# Schematic.net
KiCad netlist of a schematic drawn in EAGLE
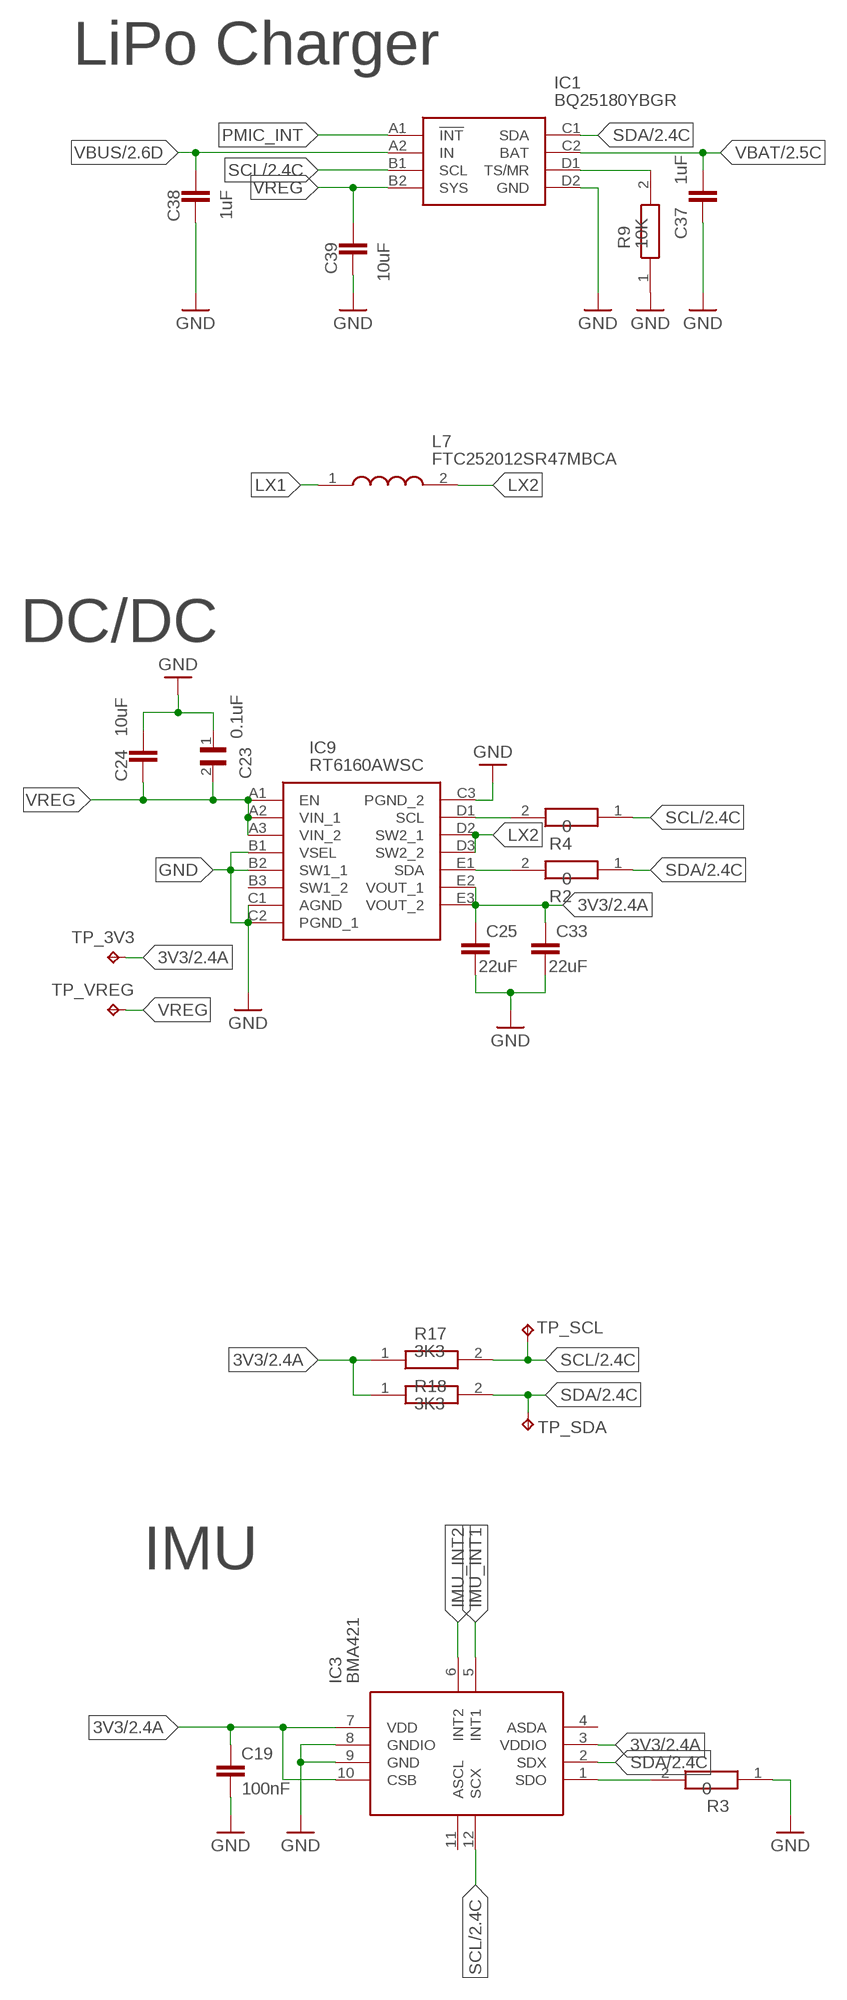
[diagram p0: schematic, sheet 1, part 1 of 2]
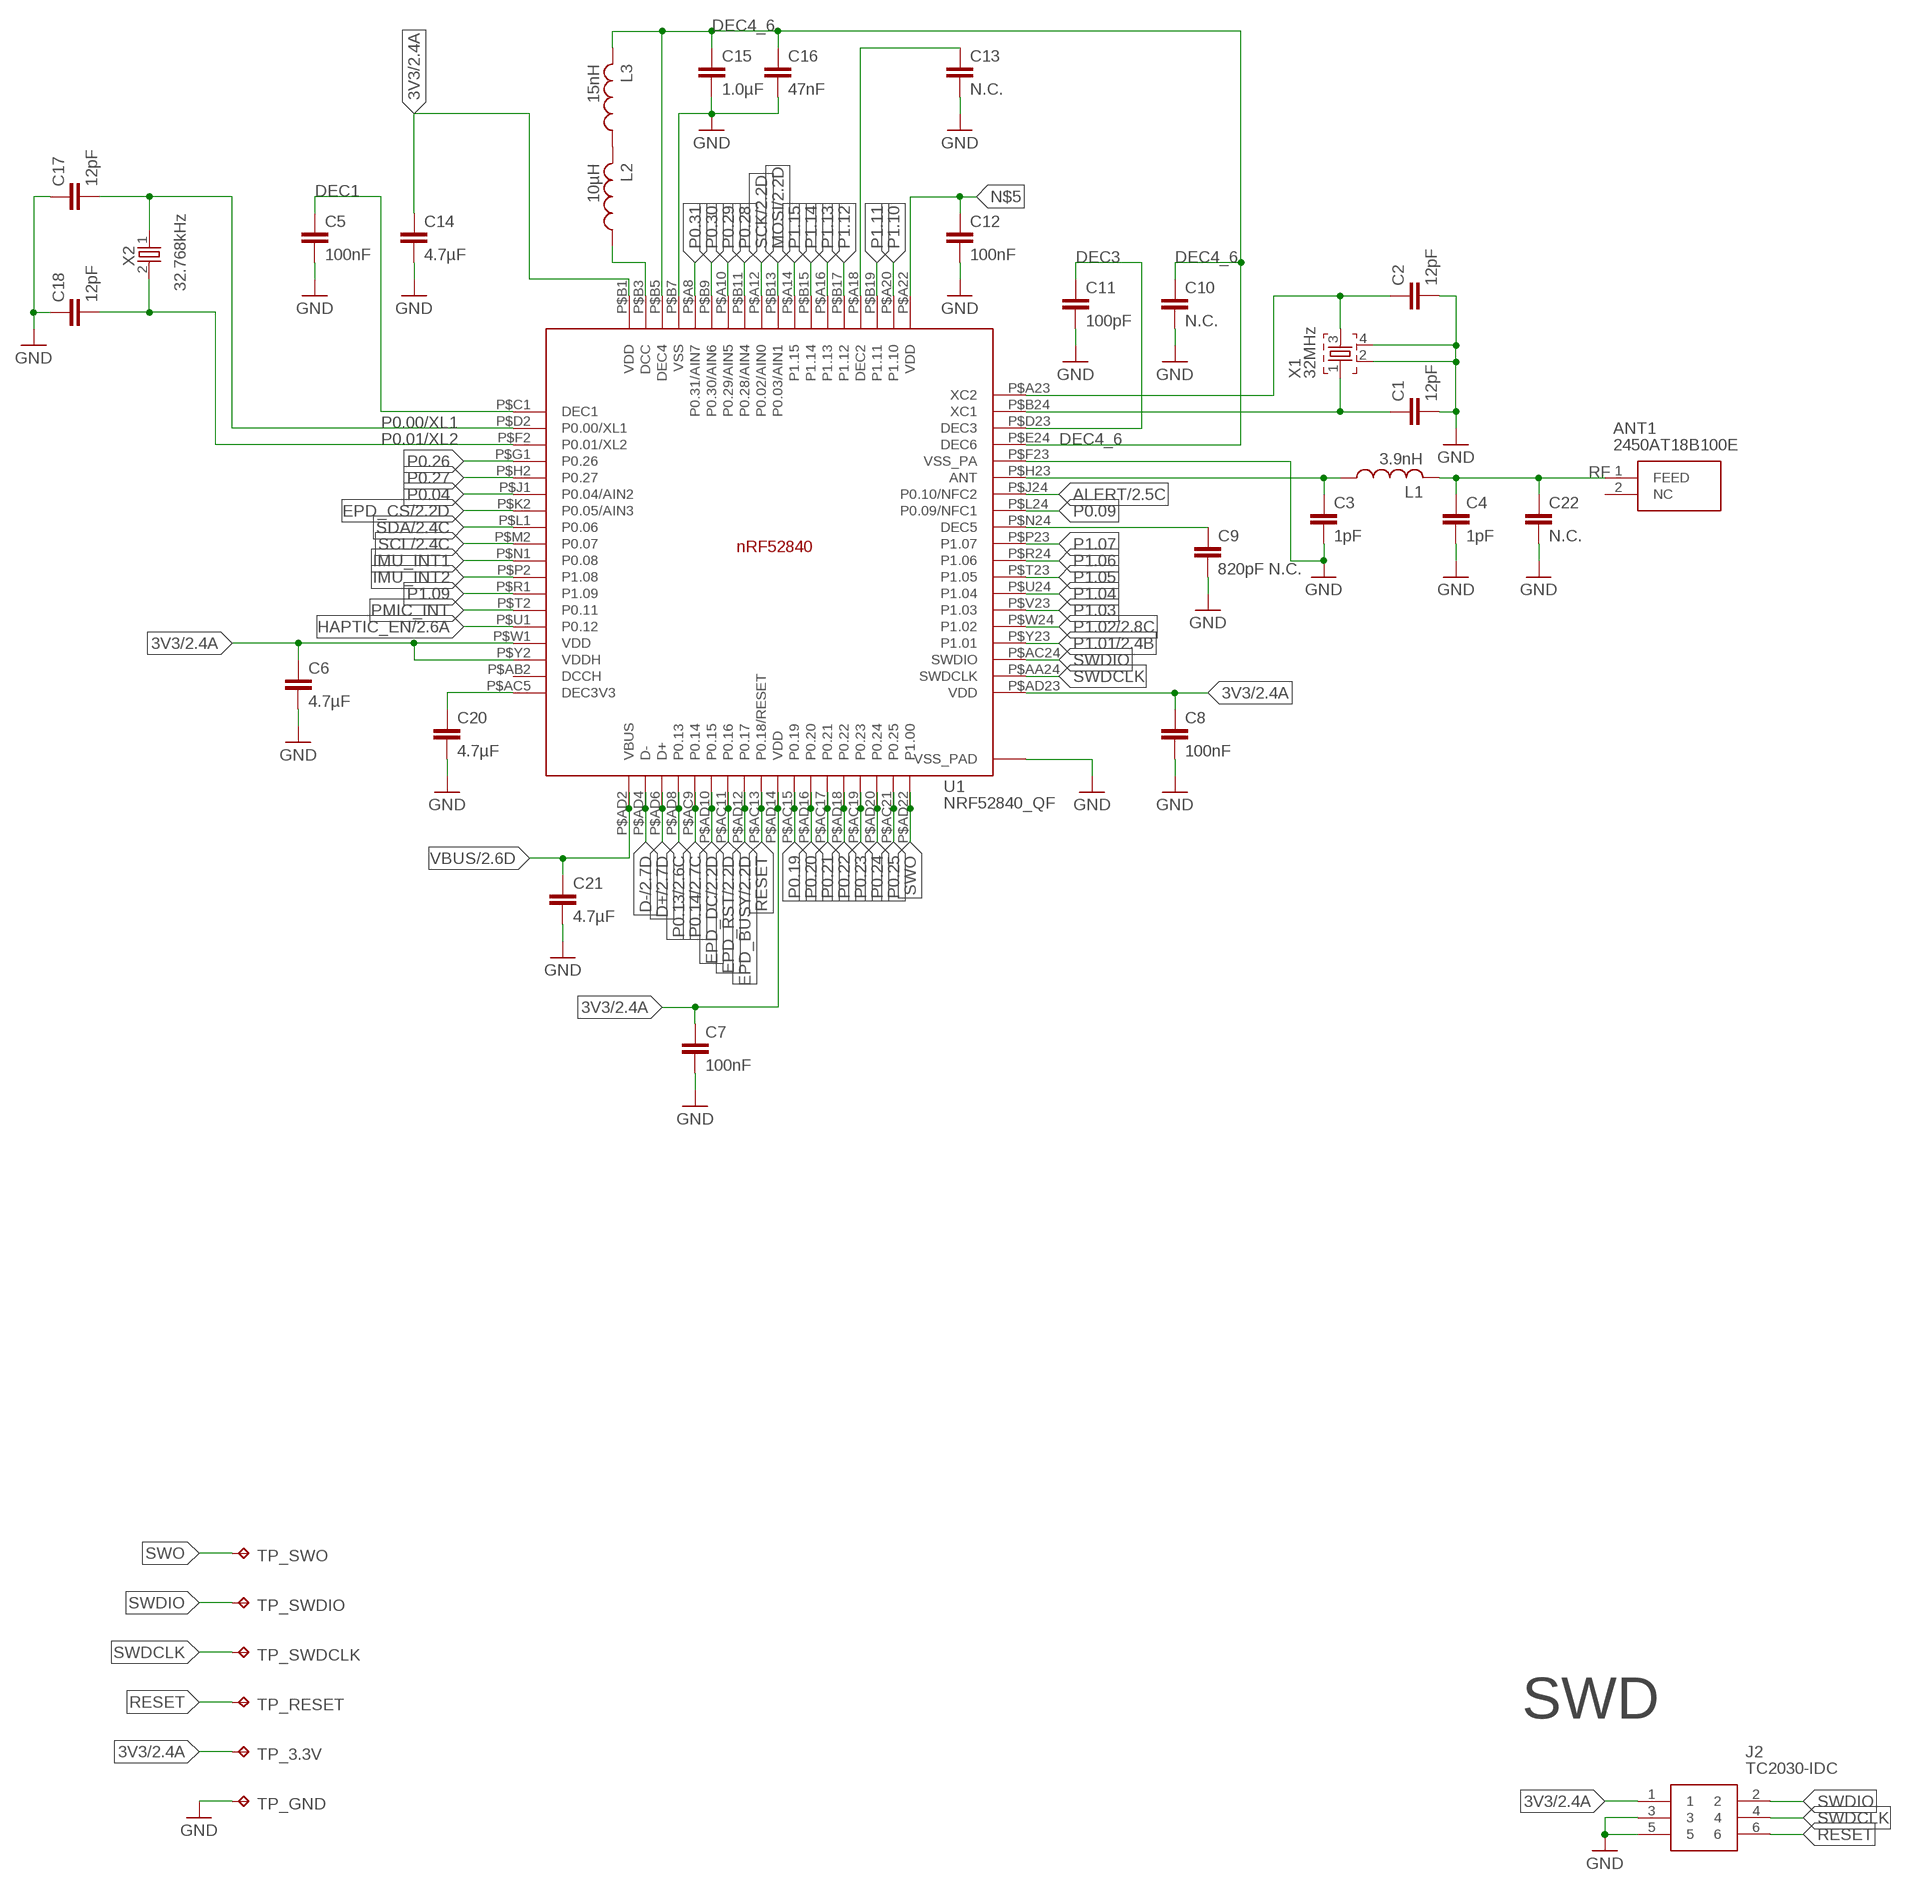
[diagram p1: schematic, sheet 1, part 2 of 2]
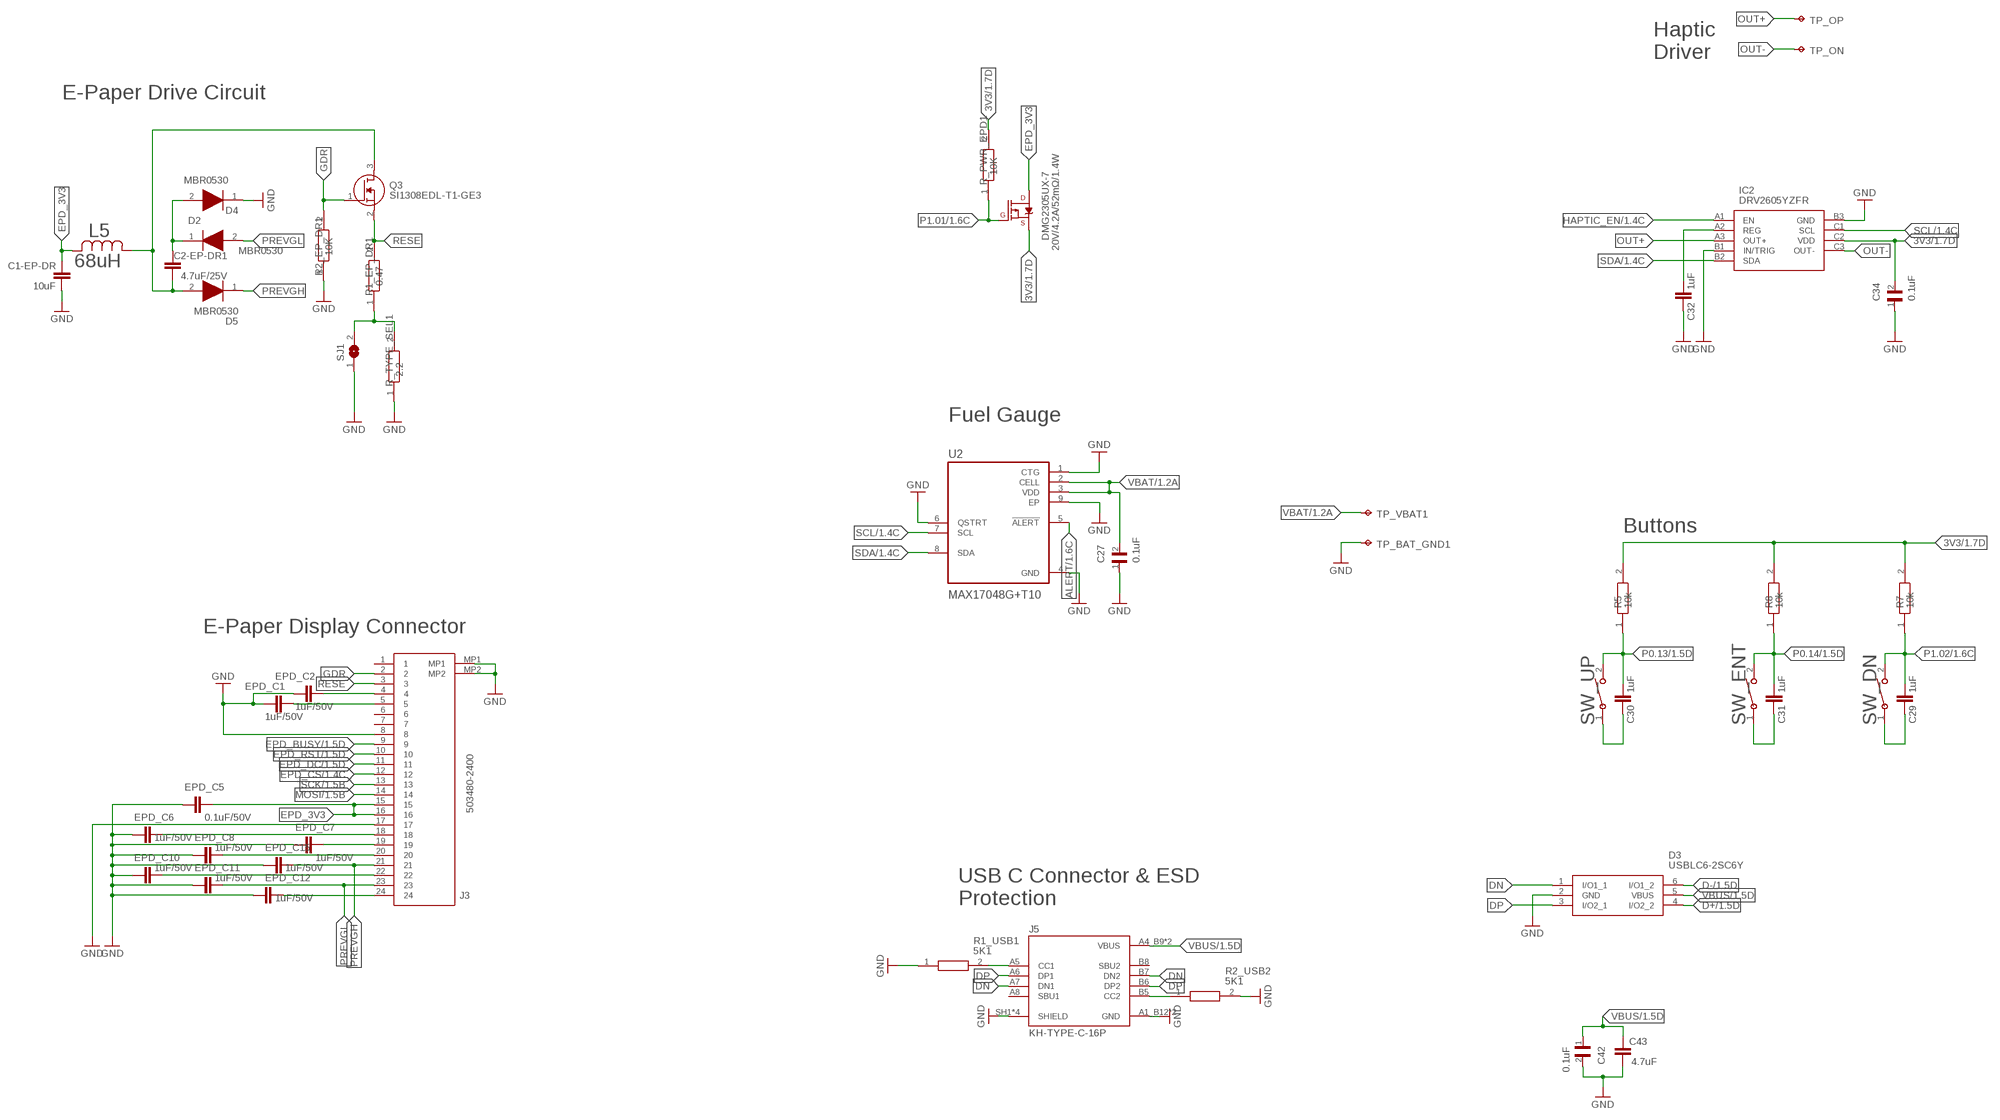
[diagram p2: schematic, sheet 2]

(export (version "E")
  (design (tool "Eeschema 10.0.6"))
  (components
    (comp (ref "ANT1")
      (value "2450AT18B100E")
      (footprint "eagle-import:2450AT18B100E_ANTC3216X140N")
      (fields (field (name "MOUSER_PART_NUMBER") "609-2450AT18B100E"))
      (libsource (lib "eagle-import") (part "2450AT18B100E_2450AT18B100E"))
    )
    (comp (ref "C1")
      (value "12pF")
      (footprint "eagle-import:NORDIC_NRF_3_RESC0201_L")
      (libsource (lib "eagle-import") (part "NORDIC_NRF_3_CAPACITOR_0201_L"))
    )
    (comp (ref "C2")
      (value "12pF")
      (footprint "eagle-import:NORDIC_NRF_3_RESC0201_L")
      (libsource (lib "eagle-import") (part "NORDIC_NRF_3_CAPACITOR_0201_L"))
    )
    (comp (ref "C3")
      (value "1pF")
      (footprint "eagle-import:NORDIC_NRF_3_RESC0201_L")
      (libsource (lib "eagle-import") (part "NORDIC_NRF_3_CAPACITOR_0201_L"))
    )
    (comp (ref "C4")
      (value "1pF")
      (footprint "eagle-import:NORDIC_NRF_3_RESC0201_L")
      (libsource (lib "eagle-import") (part "NORDIC_NRF_3_CAPACITOR_0201_L"))
    )
    (comp (ref "C5")
      (value "100nF")
      (footprint "eagle-import:NORDIC_NRF_3_RESC0201_L")
      (libsource (lib "eagle-import") (part "NORDIC_NRF_3_CAPACITOR_0201_L"))
    )
    (comp (ref "C6")
      (value "4.7µF")
      (footprint "eagle-import:PERFECT_0402_0402")
      (libsource (lib "eagle-import") (part "PERFECT_0402_CAP_0402"))
    )
    (comp (ref "C7")
      (value "100nF")
      (footprint "eagle-import:NORDIC_NRF_3_RESC0201_L")
      (libsource (lib "eagle-import") (part "NORDIC_NRF_3_CAPACITOR_0201_L"))
    )
    (comp (ref "C8")
      (value "100nF")
      (footprint "eagle-import:NORDIC_NRF_3_RESC0201_L")
      (libsource (lib "eagle-import") (part "NORDIC_NRF_3_CAPACITOR_0201_L"))
    )
    (comp (ref "C9")
      (value "820pF N.C.")
      (footprint "eagle-import:NORDIC_NRF_3_RESC0201_L")
      (libsource (lib "eagle-import") (part "NORDIC_NRF_3_CAPACITOR_0201_L"))
    )
    (comp (ref "C10")
      (value "N.C.")
      (footprint "eagle-import:PERFECT_0402_0402")
      (libsource (lib "eagle-import") (part "PERFECT_0402_CAP_0402"))
    )
    (comp (ref "C11")
      (value "100pF")
      (footprint "eagle-import:NORDIC_NRF_3_RESC0201_L")
      (libsource (lib "eagle-import") (part "NORDIC_NRF_3_CAPACITOR_0201_L"))
    )
    (comp (ref "C12")
      (value "100nF")
      (footprint "eagle-import:NORDIC_NRF_3_RESC0201_L")
      (libsource (lib "eagle-import") (part "NORDIC_NRF_3_CAPACITOR_0201_L"))
    )
    (comp (ref "C13")
      (value "N.C.")
      (footprint "eagle-import:PERFECT_0402_0402")
      (libsource (lib "eagle-import") (part "PERFECT_0402_CAP_0402"))
    )
    (comp (ref "C14")
      (value "4.7µF")
      (footprint "eagle-import:PERFECT_0402_0402")
      (libsource (lib "eagle-import") (part "PERFECT_0402_CAP_0402"))
    )
    (comp (ref "C15")
      (value "1.0µF")
      (footprint "eagle-import:PERFECT_0402_0402")
      (libsource (lib "eagle-import") (part "PERFECT_0402_CAP_0402"))
    )
    (comp (ref "C16")
      (value "47nF")
      (footprint "eagle-import:NORDIC_NRF_3_RESC0201_L")
      (libsource (lib "eagle-import") (part "NORDIC_NRF_3_CAPACITOR_0201_L"))
    )
    (comp (ref "C17")
      (value "12pF")
      (footprint "eagle-import:NORDIC_NRF_3_RESC0201_L")
      (libsource (lib "eagle-import") (part "NORDIC_NRF_3_CAPACITOR_0201_L"))
    )
    (comp (ref "C18")
      (value "12pF")
      (footprint "eagle-import:NORDIC_NRF_3_RESC0201_L")
      (libsource (lib "eagle-import") (part "NORDIC_NRF_3_CAPACITOR_0201_L"))
    )
    (comp (ref "C19")
      (value "100nF")
      (footprint "eagle-import:NORDIC_NRF_3_RESC0201_L")
      (libsource (lib "eagle-import") (part "NORDIC_NRF_3_CAPACITOR_0201_L"))
    )
    (comp (ref "C20")
      (value "4.7µF")
      (footprint "eagle-import:PERFECT_0402_0402")
      (libsource (lib "eagle-import") (part "PERFECT_0402_CAP_0402"))
    )
    (comp (ref "C21")
      (value "4.7µF")
      (footprint "eagle-import:PERFECT_0402_0402")
      (libsource (lib "eagle-import") (part "PERFECT_0402_CAP_0402"))
    )
    (comp (ref "C22")
      (value "N.C.")
      (footprint "eagle-import:PERFECT_0402_0402")
      (libsource (lib "eagle-import") (part "PERFECT_0402_CAP_0402"))
    )
    (comp (ref "C23")
      (value "0.1uF")
      (footprint "eagle-import:GRM011R60J152KE01L_1_0201")
      (libsource (lib "eagle-import") (part "GRM011R60J152KE01L_1_GRM011R60J152KE01L"))
    )
    (comp (ref "C24")
      (value "10uF")
      (footprint "eagle-import:PERFECT_0402_0402")
      (libsource (lib "eagle-import") (part "PERFECT_0402_CAP_0402"))
    )
    (comp (ref "C25")
      (value "22uF")
      (footprint "eagle-import:PERFECT_0402_0402")
      (libsource (lib "eagle-import") (part "PERFECT_0402_CAP_0402"))
    )
    (comp (ref "C33")
      (value "22uF")
      (footprint "eagle-import:PERFECT_0402_0402")
      (libsource (lib "eagle-import") (part "PERFECT_0402_CAP_0402"))
    )
    (comp (ref "C37")
      (value "1uF")
      (footprint "eagle-import:PERFECT_0402_0402")
      (libsource (lib "eagle-import") (part "PERFECT_0402_CAP_0402"))
    )
    (comp (ref "C38")
      (value "1uF")
      (footprint "eagle-import:PERFECT_0402_0402")
      (libsource (lib "eagle-import") (part "PERFECT_0402_CAP_0402"))
    )
    (comp (ref "C39")
      (value "10uF")
      (footprint "eagle-import:PERFECT_0402_0402")
      (libsource (lib "eagle-import") (part "PERFECT_0402_CAP_0402"))
    )
    (comp (ref "IC1")
      (value "BQ25180YBGR")
      (footprint "eagle-import:BQ25180YBGR_BGA8C40P2X4_100X155X50")
      (fields (field (name "MOUSER_PART_NUMBER") "595-BQ25180YBGR"))
      (libsource (lib "eagle-import") (part "BQ25180YBGR_BQ25180YBGR"))
    )
    (comp (ref "IC3")
      (value "BMA421")
      (footprint "eagle-import:BMA423_BMA423")
      (fields (field (name "ARROW_PART_NUMBER") "BMA423") (field (name "MOUSER_PART_NUMBER") "262-BMA423"))
      (libsource (lib "eagle-import") (part "BMA423_BMA423"))
    )
    (comp (ref "IC9")
      (value "RT6160AWSC")
      (footprint "eagle-import:RT6160AWSC_BGA15C40P3X5_140X230X60")
      (fields (field (name "MOUSER_PART_NUMBER") "835-RT6160AWSC"))
      (libsource (lib "eagle-import") (part "RT6160AWSC_RT6160AWSC"))
    )
    (comp (ref "J2")
      (value "TC2030-IDC")
      (footprint "eagle-import:TC2030-IDC_TC2030IDC")
      (libsource (lib "eagle-import") (part "TC2030-IDC_TC2030-IDC"))
    )
    (comp (ref "L1")
      (value "3.9nH")
      (footprint "eagle-import:NORDIC_NRF_2_RESC0402_L")
      (libsource (lib "eagle-import") (part "NORDIC_NRF_2_INDUCTOR_0402_L"))
    )
    (comp (ref "L2")
      (value "10µH")
      (footprint "eagle-import:NORDIC_NRF_2_RESC0402_L")
      (libsource (lib "eagle-import") (part "NORDIC_NRF_2_INDUCTOR_0402_L"))
    )
    (comp (ref "L3")
      (value "15nH")
      (footprint "eagle-import:NORDIC_NRF_2_RESC0402_L")
      (libsource (lib "eagle-import") (part "NORDIC_NRF_2_INDUCTOR_0402_L"))
    )
    (comp (ref "L7")
      (value "FTC252012SR47MBCA")
      (footprint "eagle-import:MLP2016SR47MT0S1_INDC2016X100N")
      (libsource (lib "eagle-import") (part "MLP2016SR47MT0S1_FTC252012SR47MBCA"))
    )
    (comp (ref "R2")
      (value "0")
      (footprint "eagle-import:CPF0201D7K68C1_0201")
      (libsource (lib "eagle-import") (part "CPF0201D7K68C1_CPF0201D7K68C1"))
    )
    (comp (ref "R3")
      (value "0")
      (footprint "eagle-import:CPF0201D7K68C1_0201")
      (libsource (lib "eagle-import") (part "CPF0201D7K68C1_CPF0201D7K68C1"))
    )
    (comp (ref "R4")
      (value "0")
      (footprint "eagle-import:CPF0201D7K68C1_0201")
      (libsource (lib "eagle-import") (part "CPF0201D7K68C1_CPF0201D7K68C1"))
    )
    (comp (ref "R9")
      (value "10K")
      (footprint "eagle-import:CPF0201D7K68C1_0201")
      (libsource (lib "eagle-import") (part "CPF0201D7K68C1_CPF0201D7K68C1"))
    )
    (comp (ref "R17")
      (value "3K3")
      (footprint "eagle-import:CPF0201D7K68C1_0201")
      (libsource (lib "eagle-import") (part "CPF0201D7K68C1_CPF0201D7K68C1"))
    )
    (comp (ref "R18")
      (value "3K3")
      (footprint "eagle-import:CPF0201D7K68C1_0201")
      (libsource (lib "eagle-import") (part "CPF0201D7K68C1_CPF0201D7K68C1"))
    )
    (comp (ref "TP_3.3V")
      (value "HECTOR_WATCH_1_TPTP20R")
      (footprint "eagle-import:HECTOR_WATCH_1_TP20R")
      (libsource (lib "eagle-import") (part "HECTOR_WATCH_1_TPTP20R"))
    )
    (comp (ref "TP_3V3")
      (value "HECTOR_WATCH_1_TPTP20R")
      (footprint "eagle-import:HECTOR_WATCH_1_TP20R")
      (libsource (lib "eagle-import") (part "HECTOR_WATCH_1_TPTP20R"))
    )
    (comp (ref "TP_GND")
      (value "HECTOR_WATCH_1_TPTP20R")
      (footprint "eagle-import:HECTOR_WATCH_1_TP20R")
      (libsource (lib "eagle-import") (part "HECTOR_WATCH_1_TPTP20R"))
    )
    (comp (ref "TP_RESET")
      (value "HECTOR_WATCH_1_TPTP20R")
      (footprint "eagle-import:HECTOR_WATCH_1_TP20R")
      (libsource (lib "eagle-import") (part "HECTOR_WATCH_1_TPTP20R"))
    )
    (comp (ref "TP_SCL")
      (value "HECTOR_WATCH_1_TPTP20R")
      (footprint "eagle-import:HECTOR_WATCH_1_TP20R")
      (libsource (lib "eagle-import") (part "HECTOR_WATCH_1_TPTP20R"))
    )
    (comp (ref "TP_SDA")
      (value "HECTOR_WATCH_1_TPTP20R")
      (footprint "eagle-import:HECTOR_WATCH_1_TP20R")
      (libsource (lib "eagle-import") (part "HECTOR_WATCH_1_TPTP20R"))
    )
    (comp (ref "TP_SWDCLK")
      (value "HECTOR_WATCH_1_TPTP20R")
      (footprint "eagle-import:HECTOR_WATCH_1_TP20R")
      (libsource (lib "eagle-import") (part "HECTOR_WATCH_1_TPTP20R"))
    )
    (comp (ref "TP_SWDIO")
      (value "HECTOR_WATCH_1_TPTP20R")
      (footprint "eagle-import:HECTOR_WATCH_1_TP20R")
      (libsource (lib "eagle-import") (part "HECTOR_WATCH_1_TPTP20R"))
    )
    (comp (ref "TP_SWO")
      (value "HECTOR_WATCH_1_TPTP20R")
      (footprint "eagle-import:HECTOR_WATCH_1_TP20R")
      (libsource (lib "eagle-import") (part "HECTOR_WATCH_1_TPTP20R"))
    )
    (comp (ref "TP_VREG")
      (value "HECTOR_WATCH_1_TPTP20R")
      (footprint "eagle-import:HECTOR_WATCH_1_TP20R")
      (libsource (lib "eagle-import") (part "HECTOR_WATCH_1_TPTP20R"))
    )
    (comp (ref "U1")
      (value "NRF52840_QF")
      (footprint "eagle-import:NORDIC_NRF_4_AQFN50P700X700X85_HS-74N")
      (libsource (lib "eagle-import") (part "NORDIC_NRF_4_NRF52840_QF"))
    )
    (comp (ref "X1")
      (value "32MHz")
      (footprint "eagle-import:NORDIC_NRF_BT-XTAL_2016_N")
      (libsource (lib "eagle-import") (part "NORDIC_NRF_XTAL_32MHZ"))
    )
    (comp (ref "X2")
      (value "32.768kHz")
      (footprint "eagle-import:NORDIC_NRF_1_XTAL_3215_N")
      (libsource (lib "eagle-import") (part "NORDIC_NRF_1_XTAL_32KHZ"))
    )
    (comp (ref "C1-EP-DR")
      (value "10uF")
      (footprint "eagle-import:PERFECT_0402_0402")
      (libsource (lib "eagle-import") (part "PERFECT_0402_CAP_0402"))
    )
    (comp (ref "C2-EP-DR1")
      (value "4.7uF/25V")
      (footprint "eagle-import:PERFECT_0402_0402")
      (libsource (lib "eagle-import") (part "PERFECT_0402_CAP_0402"))
    )
    (comp (ref "C27")
      (value "0.1uF")
      (footprint "eagle-import:GRM011R60J152KE01L_1_0201")
      (libsource (lib "eagle-import") (part "GRM011R60J152KE01L_1_GRM011R60J152KE01L"))
    )
    (comp (ref "C29")
      (value "1uF")
      (footprint "eagle-import:PERFECT_0402_0402")
      (libsource (lib "eagle-import") (part "PERFECT_0402_CAP_0402"))
    )
    (comp (ref "C30")
      (value "1uF")
      (footprint "eagle-import:PERFECT_0402_0402")
      (libsource (lib "eagle-import") (part "PERFECT_0402_CAP_0402"))
    )
    (comp (ref "C31")
      (value "1uF")
      (footprint "eagle-import:PERFECT_0402_0402")
      (libsource (lib "eagle-import") (part "PERFECT_0402_CAP_0402"))
    )
    (comp (ref "C32")
      (value "1uF")
      (footprint "eagle-import:PERFECT_0402_0402")
      (libsource (lib "eagle-import") (part "PERFECT_0402_CAP_0402"))
    )
    (comp (ref "C34")
      (value "0.1uF")
      (footprint "eagle-import:GRM011R60J152KE01L_1_0201")
      (libsource (lib "eagle-import") (part "GRM011R60J152KE01L_1_GRM011R60J152KE01L"))
    )
    (comp (ref "C42")
      (value "0.1uF")
      (footprint "eagle-import:GRM011R60J152KE01L_1_0201")
      (libsource (lib "eagle-import") (part "GRM011R60J152KE01L_1_GRM011R60J152KE01L"))
    )
    (comp (ref "C43")
      (value "4.7uF")
      (footprint "eagle-import:PERFECT_0402_0402")
      (libsource (lib "eagle-import") (part "PERFECT_0402_CAP_0402"))
    )
    (comp (ref "D2")
      (value "MBR0530")
      (footprint "eagle-import:ESP32_C6_LIBRARY_5_SOD3716X135N")
      (fields (field (name "MF") "ON Semiconductor"))
      (libsource (lib "eagle-import") (part "ESP32_C6_LIBRARY_5_MBR0530"))
    )
    (comp (ref "D3")
      (value "USBLC6-2SC6Y")
      (footprint "eagle-import:ESP32_C6_LIBRARY_3_SOT95P280X145-6N")
      (fields (field (name "MF") "STMicroelectronics"))
      (libsource (lib "eagle-import") (part "ESP32_C6_LIBRARY_3_USBLC6-2SC6Y"))
    )
    (comp (ref "D4")
      (value "MBR0530")
      (footprint "eagle-import:ESP32_C6_LIBRARY_5_SOD3716X135N")
      (fields (field (name "MF") "ON Semiconductor"))
      (libsource (lib "eagle-import") (part "ESP32_C6_LIBRARY_5_MBR0530"))
    )
    (comp (ref "D5")
      (value "MBR0530")
      (footprint "eagle-import:ESP32_C6_LIBRARY_5_SOD3716X135N")
      (fields (field (name "MF") "ON Semiconductor"))
      (libsource (lib "eagle-import") (part "ESP32_C6_LIBRARY_5_MBR0530"))
    )
    (comp (ref "DMG2305UX-7")
      (value "20V/4.2A/52mΩ/1.4W")
      (footprint "eagle-import:ESP32_C6_LIBRARY_4_ESP32_C6_LIBRARY_4_ESP32_C6_LIBRARY_4_ESP32_C6_LIBRARY_4_ESP32_WROVER_SPARKFUN-DISCRETESEMI_SOT23-3")
      (libsource (lib "eagle-import") (part "ESP32_C6_LIBRARY_4_ESP32_WROVER_SPARKFUN-DISCRETESEMI_MOSFET_PCH-DMG2305UX-7"))
    )
    (comp (ref "EPD_C1")
      (value "1uF/50V")
      (footprint "eagle-import:PERFECT_0402_0402")
      (libsource (lib "eagle-import") (part "PERFECT_0402_CAP_0402"))
    )
    (comp (ref "EPD_C2")
      (value "1uF/50V")
      (footprint "eagle-import:PERFECT_0402_0402")
      (libsource (lib "eagle-import") (part "PERFECT_0402_CAP_0402"))
    )
    (comp (ref "EPD_C5")
      (value "0.1uF/50V")
      (footprint "eagle-import:PERFECT_0402_0402")
      (libsource (lib "eagle-import") (part "PERFECT_0402_CAP_0402"))
    )
    (comp (ref "EPD_C6")
      (value "1uF/50V")
      (footprint "eagle-import:PERFECT_0402_0402")
      (libsource (lib "eagle-import") (part "PERFECT_0402_CAP_0402"))
    )
    (comp (ref "EPD_C7")
      (value "1uF/50V")
      (footprint "eagle-import:PERFECT_0402_0402")
      (libsource (lib "eagle-import") (part "PERFECT_0402_CAP_0402"))
    )
    (comp (ref "EPD_C8")
      (value "1uF/50V")
      (footprint "eagle-import:PERFECT_0402_0402")
      (libsource (lib "eagle-import") (part "PERFECT_0402_CAP_0402"))
    )
    (comp (ref "EPD_C10")
      (value "1uF/50V")
      (footprint "eagle-import:PERFECT_0402_0402")
      (libsource (lib "eagle-import") (part "PERFECT_0402_CAP_0402"))
    )
    (comp (ref "EPD_C11")
      (value "1uF/50V")
      (footprint "eagle-import:PERFECT_0402_0402")
      (libsource (lib "eagle-import") (part "PERFECT_0402_CAP_0402"))
    )
    (comp (ref "EPD_C12")
      (value "1uF/50V")
      (footprint "eagle-import:PERFECT_0402_0402")
      (libsource (lib "eagle-import") (part "PERFECT_0402_CAP_0402"))
    )
    (comp (ref "EPD_C15")
      (value "1uF/50V")
      (footprint "eagle-import:PERFECT_0402_0402")
      (libsource (lib "eagle-import") (part "PERFECT_0402_CAP_0402"))
    )
    (comp (ref "IC2")
      (value "DRV2605YZFR")
      (footprint "eagle-import:DRV2605YZFR_BGA9C50P3X3_144X144X62")
      (libsource (lib "eagle-import") (part "DRV2605YZFR_DRV2605YZFR"))
    )
    (comp (ref "J3")
      (value "503480-2400")
      (footprint "eagle-import:503480-2400_5034802400")
      (fields (field (name "MOUSER_PART_NUMBER") "538-503480-2400"))
      (libsource (lib "eagle-import") (part "503480-2400_503480-2400"))
    )
    (comp (ref "J5")
      (value "KH-TYPE-C-16P")
      (footprint "eagle-import:KH-TYPE-C-16P_KINGHELM_KH-TYPE-C-16P")
      (fields (field (name "MF") "kinghelm"))
      (libsource (lib "eagle-import") (part "KH-TYPE-C-16P_KH-TYPE-C-16P"))
    )
    (comp (ref "L5")
      (value "68uH")
      (footprint "eagle-import:ESP32_C6_LIBRARY_2_IND_4828-WE-TPC_WRE")
      (fields
        (field (name "MANUFACTURER_PART_NUMBER") "744043680")
        (field (name "COPYRIGHT") "Copyright (C) 2024 Ultra Librarian. All rights reserved.")
      )
      (libsource (lib "eagle-import") (part "ESP32_C6_LIBRARY_2_744043680IND_4828-WE-TPC_WRE"))
    )
    (comp (ref "Q3")
      (value "SI1308EDL-T1-GE3")
      (footprint "eagle-import:ESP32_C6_LIBRARY_6_SOT65P210X110-3N")
      (fields (field (name "MF") "Vishay Siliconix"))
      (libsource (lib "eagle-import") (part "ESP32_C6_LIBRARY_6_SI1308EDL-T1-GE3"))
    )
    (comp (ref "R1_EP_DR1")
      (value "0.47")
      (footprint "eagle-import:CPF0201D7K68C1_0201")
      (libsource (lib "eagle-import") (part "CPF0201D7K68C1_CPF0201D7K68C1"))
    )
    (comp (ref "R1_USB1")
      (value "5K1")
      (footprint "eagle-import:CPF0201D7K68C1_0201")
      (libsource (lib "eagle-import") (part "CPF0201D7K68C1_CPF0201D7K68C1"))
    )
    (comp (ref "R2_EP_DR1")
      (value "10K")
      (footprint "eagle-import:CPF0201D7K68C1_0201")
      (libsource (lib "eagle-import") (part "CPF0201D7K68C1_CPF0201D7K68C1"))
    )
    (comp (ref "R2_USB2")
      (value "5K1")
      (footprint "eagle-import:CPF0201D7K68C1_0201")
      (libsource (lib "eagle-import") (part "CPF0201D7K68C1_CPF0201D7K68C1"))
    )
    (comp (ref "R5")
      (value "10k")
      (footprint "eagle-import:CPF0201D7K68C1_0201")
      (libsource (lib "eagle-import") (part "CPF0201D7K68C1_CPF0201D7K68C1"))
    )
    (comp (ref "R7")
      (value "10k")
      (footprint "eagle-import:CPF0201D7K68C1_0201")
      (libsource (lib "eagle-import") (part "CPF0201D7K68C1_CPF0201D7K68C1"))
    )
    (comp (ref "R8")
      (value "10k")
      (footprint "eagle-import:CPF0201D7K68C1_0201")
      (libsource (lib "eagle-import") (part "CPF0201D7K68C1_CPF0201D7K68C1"))
    )
    (comp (ref "R_PWR_EPD1")
      (value "10K")
      (footprint "eagle-import:CPF0201D7K68C1_0201")
      (libsource (lib "eagle-import") (part "CPF0201D7K68C1_CPF0201D7K68C1"))
    )
    (comp (ref "R_TYPE_SEL1")
      (value "2.2")
      (footprint "eagle-import:CPF0201D7K68C1_0201")
      (libsource (lib "eagle-import") (part "CPF0201D7K68C1_CPF0201D7K68C1"))
    )
    (comp (ref "SJ1")
      (value "ESP32_C6_LIBRARY_7_JUMPER_SJ")
      (footprint "eagle-import:ESP32_C6_LIBRARY_7_JUMPER_SJ")
      (libsource (lib "eagle-import") (part "ESP32_C6_LIBRARY_7_JUMPER_SJ"))
    )
    (comp (ref "SW_DN")
      (value "2025-10-22_07-23-44_LIBRARY_EVP-AKE31ASW_EVP-AKE31A_PAN")
      (footprint "eagle-import:2025-10-22_07-23-44_LIBRARY_SW_EVP-AKE31A_PAN")
      (fields
        (field (name "MANUFACTURER_PART_NUMBER") "EVP-AKE31A")
        (field (name "COPYRIGHT") "Copyright (C) 2025 Ultra Librarian. All rights reserved.")
      )
      (libsource (lib "eagle-import") (part "2025-10-22_07-23-44_LIBRARY_EVP-AKE31ASW_EVP-AKE31A_PAN"))
    )
    (comp (ref "SW_ENT")
      (value "2025-10-22_07-23-44_LIBRARY_EVP-AKE31ASW_EVP-AKE31A_PAN")
      (footprint "eagle-import:2025-10-22_07-23-44_LIBRARY_SW_EVP-AKE31A_PAN")
      (fields
        (field (name "MANUFACTURER_PART_NUMBER") "EVP-AKE31A")
        (field (name "COPYRIGHT") "Copyright (C) 2025 Ultra Librarian. All rights reserved.")
      )
      (libsource (lib "eagle-import") (part "2025-10-22_07-23-44_LIBRARY_EVP-AKE31ASW_EVP-AKE31A_PAN"))
    )
    (comp (ref "SW_UP")
      (value "2025-10-22_07-23-44_LIBRARY_EVP-AKE31ASW_EVP-AKE31A_PAN")
      (footprint "eagle-import:2025-10-22_07-23-44_LIBRARY_SW_EVP-AKE31A_PAN")
      (fields
        (field (name "MANUFACTURER_PART_NUMBER") "EVP-AKE31A")
        (field (name "COPYRIGHT") "Copyright (C) 2025 Ultra Librarian. All rights reserved.")
      )
      (libsource (lib "eagle-import") (part "2025-10-22_07-23-44_LIBRARY_EVP-AKE31ASW_EVP-AKE31A_PAN"))
    )
    (comp (ref "TP_BAT_GND1")
      (value "HECTOR_WATCH_1_TPTP20R")
      (footprint "eagle-import:HECTOR_WATCH_1_TP20R")
      (libsource (lib "eagle-import") (part "HECTOR_WATCH_1_TPTP20R"))
    )
    (comp (ref "TP_ON")
      (value "HECTOR_WATCH_1_TPTP20R")
      (footprint "eagle-import:HECTOR_WATCH_1_TP20R")
      (libsource (lib "eagle-import") (part "HECTOR_WATCH_1_TPTP20R"))
    )
    (comp (ref "TP_OP")
      (value "HECTOR_WATCH_1_TPTP20R")
      (footprint "eagle-import:HECTOR_WATCH_1_TP20R")
      (libsource (lib "eagle-import") (part "HECTOR_WATCH_1_TPTP20R"))
    )
    (comp (ref "TP_VBAT1")
      (value "HECTOR_WATCH_1_TPTP20R")
      (footprint "eagle-import:HECTOR_WATCH_1_TP20R")
      (libsource (lib "eagle-import") (part "HECTOR_WATCH_1_TPTP20R"))
    )
    (comp (ref "U2")
      (value "MAX17048G+T10")
      (footprint "eagle-import:ESP32_C6_LIBRARY_SON50P200X200X80-9N")
      (fields (field (name "MF") "Analog Devices"))
      (libsource (lib "eagle-import") (part "ESP32_C6_LIBRARY_MAX17048G+T10"))
    )
  )
  (nets
    (net (code "1") (name "3V3{slash}1.7D") (class "Default")
      (node (ref "C34") (pin "2") (pinfunction "2_2") (pintype "passive"))
      (node (ref "DMG2305UX-7") (pin "2") (pinfunction "S_2") (pintype "bidirectional"))
      (node (ref "IC2") (pin "C2") (pinfunction "VDD_C2") (pintype "bidirectional"))
      (node (ref "R5") (pin "2") (pinfunction "2_2") (pintype "bidirectional"))
      (node (ref "R7") (pin "2") (pinfunction "2_2") (pintype "bidirectional"))
      (node (ref "R8") (pin "2") (pinfunction "2_2") (pintype "bidirectional"))
      (node (ref "R_PWR_EPD1") (pin "2") (pinfunction "2_2") (pintype "bidirectional"))
    )
    (net (code "2") (name "3V3{slash}2.4A") (class "Default")
      (node (ref "C14") (pin "1") (pinfunction "1_1") (pintype "passive"))
      (node (ref "C19") (pin "2") (pinfunction "2_2") (pintype "passive"))
      (node (ref "C25") (pin "2") (pinfunction "2_2") (pintype "passive"))
      (node (ref "C33") (pin "2") (pinfunction "2_2") (pintype "passive"))
      (node (ref "C6") (pin "1") (pinfunction "1_1") (pintype "passive"))
      (node (ref "C7") (pin "1") (pinfunction "1_1") (pintype "passive"))
      (node (ref "C8") (pin "1") (pinfunction "1_1") (pintype "passive"))
      (node (ref "IC3") (pin "10") (pinfunction "CSB_10") (pintype "bidirectional"))
      (node (ref "IC3") (pin "3") (pinfunction "VDDIO_3") (pintype "bidirectional"))
      (node (ref "IC3") (pin "7") (pinfunction "VDD_7") (pintype "bidirectional"))
      (node (ref "IC9") (pin "E2") (pinfunction "VOUT_1_E2") (pintype "bidirectional"))
      (node (ref "IC9") (pin "E3") (pinfunction "VOUT_2_E3") (pintype "bidirectional"))
      (node (ref "J2") (pin "1") (pinfunction "1_1") (pintype "bidirectional"))
      (node (ref "R17") (pin "1") (pinfunction "1_1") (pintype "bidirectional"))
      (node (ref "R18") (pin "1") (pinfunction "1_1") (pintype "bidirectional"))
      (node (ref "TP_3.3V") (pin "TP") (pinfunction "TP_TP") (pintype "input"))
      (node (ref "TP_3V3") (pin "TP") (pinfunction "TP_TP") (pintype "input"))
      (node (ref "U1") (pin "P$AD14") (pinfunction "VDD_P$AD14") (pintype "power_in"))
      (node (ref "U1") (pin "P$AD23") (pinfunction "VDD_P$AD23") (pintype "power_in"))
      (node (ref "U1") (pin "P$B1") (pinfunction "VDD_P$B1") (pintype "power_in"))
      (node (ref "U1") (pin "P$W1") (pinfunction "VDD_P$W1") (pintype "power_in"))
      (node (ref "U1") (pin "P$Y2") (pinfunction "VDDH_P$Y2") (pintype "power_in"))
    )
    (net (code "3") (name "ALERT{slash}1.6C") (class "Default")
      (node (ref "U2") (pin "5") (pinfunction "~{ALERT}_5") (pintype "output"))
    )
    (net (code "4") (name "ALERT{slash}2.5C") (class "Default")
      (node (ref "U1") (pin "P$J24") (pinfunction "P0.10/NFC2_P$J24") (pintype "bidirectional"))
    )
    (net (code "5") (name "D+{slash}1.5D") (class "Default")
      (node (ref "D3") (pin "4") (pinfunction "I/O2_2_4") (pintype "bidirectional"))
    )
    (net (code "6") (name "D+{slash}2.7D") (class "Default")
      (node (ref "U1") (pin "P$AD6") (pinfunction "D+_P$AD6") (pintype "bidirectional"))
    )
    (net (code "7") (name "D-{slash}1.5D") (class "Default")
      (node (ref "D3") (pin "6") (pinfunction "I/O1_2_6") (pintype "bidirectional"))
    )
    (net (code "8") (name "D-{slash}2.7D") (class "Default")
      (node (ref "U1") (pin "P$AD4") (pinfunction "D-_P$AD4") (pintype "bidirectional"))
    )
    (net (code "9") (name "DEC1") (class "Default")
      (node (ref "C5") (pin "1") (pinfunction "1_1") (pintype "passive"))
      (node (ref "U1") (pin "P$C1") (pinfunction "DEC1_P$C1") (pintype "power_in"))
    )
    (net (code "10") (name "DEC3") (class "Default")
      (node (ref "C11") (pin "1") (pinfunction "1_1") (pintype "passive"))
      (node (ref "U1") (pin "P$D23") (pinfunction "DEC3_P$D23") (pintype "bidirectional"))
    )
    (net (code "11") (name "DEC4_6") (class "Default")
      (node (ref "C10") (pin "1") (pinfunction "1_1") (pintype "passive"))
      (node (ref "C15") (pin "1") (pinfunction "1_1") (pintype "passive"))
      (node (ref "C16") (pin "1") (pinfunction "1_1") (pintype "passive"))
      (node (ref "L3") (pin "2") (pinfunction "2_2") (pintype "passive"))
      (node (ref "U1") (pin "P$B5") (pinfunction "DEC4_P$B5") (pintype "power_in"))
      (node (ref "U1") (pin "P$E24") (pinfunction "DEC6_P$E24") (pintype "bidirectional"))
    )
    (net (code "12") (name "DN") (class "Default")
      (node (ref "D3") (pin "1") (pinfunction "I/O1_1_1") (pintype "bidirectional"))
      (node (ref "J5") (pin "A7") (pinfunction "DN1_A7") (pintype "bidirectional"))
      (node (ref "J5") (pin "B7") (pinfunction "DN2_B7") (pintype "bidirectional"))
    )
    (net (code "13") (name "DP") (class "Default")
      (node (ref "D3") (pin "3") (pinfunction "I/O2_1_3") (pintype "bidirectional"))
      (node (ref "J5") (pin "A6") (pinfunction "DP1_A6") (pintype "bidirectional"))
      (node (ref "J5") (pin "B6") (pinfunction "DP2_B6") (pintype "bidirectional"))
    )
    (net (code "14") (name "EPD_3V3") (class "Default")
      (node (ref "C1-EP-DR") (pin "2") (pinfunction "2_2") (pintype "passive"))
      (node (ref "DMG2305UX-7") (pin "3") (pinfunction "D_3") (pintype "bidirectional"))
      (node (ref "EPD_C5") (pin "1") (pinfunction "1_1") (pintype "passive"))
      (node (ref "J3") (pin "15") (pinfunction "15_15") (pintype "bidirectional"))
      (node (ref "J3") (pin "16") (pinfunction "16_16") (pintype "bidirectional"))
      (node (ref "L5") (pin "2") (pinfunction "2_2") (pintype "passive"))
    )
    (net (code "15") (name "EPD_BUSY{slash}1.5D") (class "Default")
      (node (ref "J3") (pin "9") (pinfunction "9_9") (pintype "bidirectional"))
    )
    (net (code "16") (name "EPD_BUSY{slash}2.2D") (class "Default")
      (node (ref "U1") (pin "P$AD12") (pinfunction "P0.17_P$AD12") (pintype "bidirectional"))
    )
    (net (code "17") (name "EPD_CS{slash}1.4C") (class "Default")
      (node (ref "J3") (pin "12") (pinfunction "12_12") (pintype "bidirectional"))
    )
    (net (code "18") (name "EPD_CS{slash}2.2D") (class "Default")
      (node (ref "U1") (pin "P$K2") (pinfunction "P0.05/AIN3_P$K2") (pintype "bidirectional"))
    )
    (net (code "19") (name "EPD_DC{slash}1.5D") (class "Default")
      (node (ref "J3") (pin "11") (pinfunction "11_11") (pintype "bidirectional"))
    )
    (net (code "20") (name "EPD_DC{slash}2.2D") (class "Default")
      (node (ref "U1") (pin "P$AD10") (pinfunction "P0.15_P$AD10") (pintype "bidirectional"))
    )
    (net (code "21") (name "EPD_RST{slash}1.5D") (class "Default")
      (node (ref "J3") (pin "10") (pinfunction "10_10") (pintype "bidirectional"))
    )
    (net (code "22") (name "EPD_RST{slash}2.2D") (class "Default")
      (node (ref "U1") (pin "P$AC11") (pinfunction "P0.16_P$AC11") (pintype "bidirectional"))
    )
    (net (code "23") (name "GDR") (class "Default")
      (node (ref "J3") (pin "2") (pinfunction "2_2") (pintype "bidirectional"))
      (node (ref "Q3") (pin "1") (pinfunction "G_1") (pintype "bidirectional"))
      (node (ref "R2_EP_DR1") (pin "2") (pinfunction "2_2") (pintype "bidirectional"))
    )
    (net (code "24") (name "GND") (class "Default")
      (node (ref "C1") (pin "2") (pinfunction "2_2") (pintype "passive"))
      (node (ref "C1-EP-DR") (pin "1") (pinfunction "1_1") (pintype "passive"))
      (node (ref "C10") (pin "2") (pinfunction "2_2") (pintype "passive"))
      (node (ref "C11") (pin "2") (pinfunction "2_2") (pintype "passive"))
      (node (ref "C12") (pin "2") (pinfunction "2_2") (pintype "passive"))
      (node (ref "C13") (pin "2") (pinfunction "2_2") (pintype "passive"))
      (node (ref "C14") (pin "2") (pinfunction "2_2") (pintype "passive"))
      (node (ref "C15") (pin "2") (pinfunction "2_2") (pintype "passive"))
      (node (ref "C16") (pin "2") (pinfunction "2_2") (pintype "passive"))
      (node (ref "C17") (pin "1") (pinfunction "1_1") (pintype "passive"))
      (node (ref "C18") (pin "1") (pinfunction "1_1") (pintype "passive"))
      (node (ref "C19") (pin "1") (pinfunction "1_1") (pintype "passive"))
      (node (ref "C2") (pin "2") (pinfunction "2_2") (pintype "passive"))
      (node (ref "C20") (pin "2") (pinfunction "2_2") (pintype "passive"))
      (node (ref "C21") (pin "2") (pinfunction "2_2") (pintype "passive"))
      (node (ref "C22") (pin "2") (pinfunction "2_2") (pintype "passive"))
      (node (ref "C23") (pin "1") (pinfunction "1_1") (pintype "passive"))
      (node (ref "C24") (pin "2") (pinfunction "2_2") (pintype "passive"))
      (node (ref "C25") (pin "1") (pinfunction "1_1") (pintype "passive"))
      (node (ref "C27") (pin "1") (pinfunction "1_1") (pintype "passive"))
      (node (ref "C3") (pin "2") (pinfunction "2_2") (pintype "passive"))
      (node (ref "C32") (pin "1") (pinfunction "1_1") (pintype "passive"))
      (node (ref "C33") (pin "1") (pinfunction "1_1") (pintype "passive"))
      (node (ref "C34") (pin "1") (pinfunction "1_1") (pintype "passive"))
      (node (ref "C37") (pin "1") (pinfunction "1_1") (pintype "passive"))
      (node (ref "C38") (pin "1") (pinfunction "1_1") (pintype "passive"))
      (node (ref "C39") (pin "1") (pinfunction "1_1") (pintype "passive"))
      (node (ref "C4") (pin "2") (pinfunction "2_2") (pintype "passive"))
      (node (ref "C42") (pin "2") (pinfunction "2_2") (pintype "passive"))
      (node (ref "C43") (pin "1") (pinfunction "1_1") (pintype "passive"))
      (node (ref "C5") (pin "2") (pinfunction "2_2") (pintype "passive"))
      (node (ref "C6") (pin "2") (pinfunction "2_2") (pintype "passive"))
      (node (ref "C7") (pin "2") (pinfunction "2_2") (pintype "passive"))
      (node (ref "C8") (pin "2") (pinfunction "2_2") (pintype "passive"))
      (node (ref "C9") (pin "2") (pinfunction "2_2") (pintype "passive"))
      (node (ref "D3") (pin "2") (pinfunction "GND_2") (pintype "bidirectional"))
      (node (ref "D4") (pin "1") (pinfunction "K_1") (pintype "bidirectional"))
      (node (ref "EPD_C1") (pin "2") (pinfunction "2_2") (pintype "passive"))
      (node (ref "EPD_C10") (pin "2") (pinfunction "2_2") (pintype "passive"))
      (node (ref "EPD_C11") (pin "2") (pinfunction "2_2") (pintype "passive"))
      (node (ref "EPD_C12") (pin "2") (pinfunction "2_2") (pintype "passive"))
      (node (ref "EPD_C15") (pin "2") (pinfunction "2_2") (pintype "passive"))
      (node (ref "EPD_C2") (pin "2") (pinfunction "2_2") (pintype "passive"))
      (node (ref "EPD_C5") (pin "2") (pinfunction "2_2") (pintype "passive"))
      (node (ref "EPD_C6") (pin "2") (pinfunction "2_2") (pintype "passive"))
      (node (ref "EPD_C7") (pin "2") (pinfunction "2_2") (pintype "passive"))
      (node (ref "EPD_C8") (pin "2") (pinfunction "2_2") (pintype "passive"))
      (node (ref "IC1") (pin "D2") (pinfunction "GND_D2") (pintype "bidirectional"))
      (node (ref "IC2") (pin "B1") (pinfunction "IN/TRIG_B1") (pintype "bidirectional"))
      (node (ref "IC2") (pin "B3") (pinfunction "GND_B3") (pintype "bidirectional"))
      (node (ref "IC3") (pin "8") (pinfunction "GNDIO_8") (pintype "bidirectional"))
      (node (ref "IC3") (pin "9") (pinfunction "GND_9") (pintype "bidirectional"))
      (node (ref "IC9") (pin "B1") (pinfunction "VSEL_B1") (pintype "bidirectional"))
      (node (ref "IC9") (pin "B2") (pinfunction "SW1_1_B2") (pintype "bidirectional"))
      (node (ref "IC9") (pin "C1") (pinfunction "AGND_C1") (pintype "bidirectional"))
      (node (ref "IC9") (pin "C2") (pinfunction "PGND_1_C2") (pintype "bidirectional"))
      (node (ref "IC9") (pin "C3") (pinfunction "PGND_2_C3") (pintype "bidirectional"))
      (node (ref "J2") (pin "3") (pinfunction "3_3") (pintype "bidirectional"))
      (node (ref "J2") (pin "5") (pinfunction "5_5") (pintype "bidirectional"))
      (node (ref "J3") (pin "17") (pinfunction "17_17") (pintype "bidirectional"))
      (node (ref "J3") (pin "8") (pinfunction "8_8") (pintype "bidirectional"))
      (node (ref "J3") (pin "MP1") (pinfunction "MP1_MP1") (pintype "bidirectional"))
      (node (ref "J3") (pin "MP2") (pinfunction "MP2_MP2") (pintype "bidirectional"))
      (node (ref "J5") (pin "A12_B1") (pinfunction "GND_A12_B1") (pintype "power_in"))
      (node (ref "J5") (pin "A1_B12") (pinfunction "GND_A1_B12") (pintype "power_in"))
      (node (ref "J5") (pin "SH1") (pinfunction "SHIELD_SH1") (pintype "passive"))
      (node (ref "J5") (pin "SH2") (pinfunction "SHIELD_SH2") (pintype "passive"))
      (node (ref "J5") (pin "SH3") (pinfunction "SHIELD_SH3") (pintype "passive"))
      (node (ref "J5") (pin "SH4") (pinfunction "SHIELD_SH4") (pintype "passive"))
      (node (ref "R1_USB1") (pin "1") (pinfunction "1_1") (pintype "bidirectional"))
      (node (ref "R2_EP_DR1") (pin "1") (pinfunction "1_1") (pintype "bidirectional"))
      (node (ref "R2_USB2") (pin "2") (pinfunction "2_2") (pintype "bidirectional"))
      (node (ref "R3") (pin "1") (pinfunction "1_1") (pintype "bidirectional"))
      (node (ref "R9") (pin "1") (pinfunction "1_1") (pintype "bidirectional"))
      (node (ref "R_TYPE_SEL1") (pin "1") (pinfunction "1_1") (pintype "bidirectional"))
      (node (ref "SJ1") (pin "1") (pinfunction "1_1") (pintype "passive"))
      (node (ref "TP_BAT_GND1") (pin "TP") (pinfunction "TP_TP") (pintype "input"))
      (node (ref "TP_GND") (pin "TP") (pinfunction "TP_TP") (pintype "input"))
      (node (ref "U1") (pin "P$74") (pinfunction "VSS_PAD_P$74") (pintype "bidirectional"))
      (node (ref "U1") (pin "P$75") (pinfunction "VSS_PAD_P$75") (pintype "bidirectional"))
      (node (ref "U1") (pin "P$76") (pinfunction "VSS_PAD_P$76") (pintype "bidirectional"))
      (node (ref "U1") (pin "P$77") (pinfunction "VSS_PAD_P$77") (pintype "bidirectional"))
      (node (ref "U1") (pin "P$78") (pinfunction "VSS_PAD_P$78") (pintype "bidirectional"))
      (node (ref "U1") (pin "P$79") (pinfunction "VSS_PAD_P$79") (pintype "bidirectional"))
      (node (ref "U1") (pin "P$80") (pinfunction "VSS_PAD_P$80") (pintype "bidirectional"))
      (node (ref "U1") (pin "P$81") (pinfunction "VSS_PAD_P$81") (pintype "bidirectional"))
      (node (ref "U1") (pin "P$82") (pinfunction "VSS_PAD_P$82") (pintype "bidirectional"))
      (node (ref "U1") (pin "P$83") (pinfunction "VSS_PAD_P$83") (pintype "bidirectional"))
      (node (ref "U1") (pin "P$84") (pinfunction "VSS_PAD_P$84") (pintype "bidirectional"))
      (node (ref "U1") (pin "P$85") (pinfunction "VSS_PAD_P$85") (pintype "bidirectional"))
      (node (ref "U1") (pin "P$86") (pinfunction "VSS_PAD_P$86") (pintype "bidirectional"))
      (node (ref "U1") (pin "P$87") (pinfunction "VSS_PAD_P$87") (pintype "bidirectional"))
      (node (ref "U1") (pin "P$88") (pinfunction "VSS_PAD_P$88") (pintype "bidirectional"))
      (node (ref "U1") (pin "P$89") (pinfunction "VSS_PAD_P$89") (pintype "bidirectional"))
      (node (ref "U1") (pin "P$90") (pinfunction "VSS_PAD_P$90") (pintype "bidirectional"))
      (node (ref "U1") (pin "P$B7") (pinfunction "VSS_P$B7") (pintype "power_in"))
      (node (ref "U1") (pin "P$F23") (pinfunction "VSS_PA_P$F23") (pintype "bidirectional"))
      (node (ref "U2") (pin "1") (pinfunction "CTG_1") (pintype "power_in"))
      (node (ref "U2") (pin "4") (pinfunction "GND_4") (pintype "power_in"))
      (node (ref "U2") (pin "6") (pinfunction "QSTRT_6") (pintype "input"))
      (node (ref "U2") (pin "9") (pinfunction "EP_9") (pintype "power_in"))
      (node (ref "X1") (pin "2") (pinfunction "2_2") (pintype "passive"))
      (node (ref "X1") (pin "4") (pinfunction "4_4") (pintype "passive"))
    )
    (net (code "25") (name "HAPTIC_EN{slash}1.4C") (class "Default")
      (node (ref "IC2") (pin "A1") (pinfunction "EN_A1") (pintype "bidirectional"))
    )
    (net (code "26") (name "HAPTIC_EN{slash}2.6A") (class "Default")
      (node (ref "U1") (pin "P$U1") (pinfunction "P0.12_P$U1") (pintype "bidirectional"))
    )
    (net (code "27") (name "IMU_INT1") (class "Default")
      (node (ref "IC3") (pin "5") (pinfunction "INT1_5") (pintype "bidirectional"))
      (node (ref "U1") (pin "P$N1") (pinfunction "P0.08_P$N1") (pintype "bidirectional"))
    )
    (net (code "28") (name "IMU_INT2") (class "Default")
      (node (ref "IC3") (pin "6") (pinfunction "INT2_6") (pintype "bidirectional"))
      (node (ref "U1") (pin "P$P2") (pinfunction "P1.08_P$P2") (pintype "bidirectional"))
    )
    (net (code "29") (name "LX1") (class "Default")
      (node (ref "L7") (pin "1") (pinfunction "1_1") (pintype "bidirectional"))
    )
    (net (code "30") (name "LX2") (class "Default")
      (node (ref "IC9") (pin "D2") (pinfunction "SW2_1_D2") (pintype "bidirectional"))
      (node (ref "IC9") (pin "D3") (pinfunction "SW2_2_D3") (pintype "bidirectional"))
      (node (ref "L7") (pin "2") (pinfunction "2_2") (pintype "bidirectional"))
    )
    (net (code "31") (name "MOSI{slash}1.5B") (class "Default")
      (node (ref "J3") (pin "14") (pinfunction "14_14") (pintype "bidirectional"))
    )
    (net (code "32") (name "MOSI{slash}2.2D") (class "Default")
      (node (ref "U1") (pin "P$B13") (pinfunction "P0.03/AIN1_P$B13") (pintype "bidirectional"))
    )
    (net (code "33") (name "N$5") (class "Default")
      (node (ref "C12") (pin "1") (pinfunction "1_1") (pintype "passive"))
      (node (ref "U1") (pin "P$A22") (pinfunction "VDD_P$A22") (pintype "power_in"))
    )
    (net (code "34") (name "Net-(C29-Pad1)") (class "Default")
      (node (ref "C29") (pin "1") (pinfunction "1_1") (pintype "passive"))
      (node (ref "SW_DN") (pin "1") (pinfunction "1_1") (pintype "passive"))
    )
    (net (code "35") (name "Net-(C30-Pad1)") (class "Default")
      (node (ref "C30") (pin "1") (pinfunction "1_1") (pintype "passive"))
      (node (ref "SW_UP") (pin "1") (pinfunction "1_1") (pintype "passive"))
    )
    (net (code "36") (name "Net-(C31-Pad1)") (class "Default")
      (node (ref "C31") (pin "1") (pinfunction "1_1") (pintype "passive"))
      (node (ref "SW_ENT") (pin "1") (pinfunction "1_1") (pintype "passive"))
    )
    (net (code "37") (name "Net-(D2-K)") (class "Default")
      (node (ref "C2-EP-DR1") (pin "2") (pinfunction "2_2") (pintype "passive"))
      (node (ref "D2") (pin "1") (pinfunction "K_1") (pintype "bidirectional"))
      (node (ref "D4") (pin "2") (pinfunction "A_2") (pintype "bidirectional"))
    )
    (net (code "38") (name "Net-(D5-A)") (class "Default")
      (node (ref "C2-EP-DR1") (pin "1") (pinfunction "1_1") (pintype "passive"))
      (node (ref "D5") (pin "2") (pinfunction "A_2") (pintype "bidirectional"))
      (node (ref "L5") (pin "1") (pinfunction "1_1") (pintype "passive"))
      (node (ref "Q3") (pin "3") (pinfunction "D_3") (pintype "bidirectional"))
    )
    (net (code "39") (name "Net-(EPD_C1-Pad1)") (class "Default")
      (node (ref "EPD_C1") (pin "1") (pinfunction "1_1") (pintype "passive"))
      (node (ref "J3") (pin "5") (pinfunction "5_5") (pintype "bidirectional"))
    )
    (net (code "40") (name "Net-(EPD_C2-Pad1)") (class "Default")
      (node (ref "EPD_C2") (pin "1") (pinfunction "1_1") (pintype "passive"))
      (node (ref "J3") (pin "4") (pinfunction "4_4") (pintype "bidirectional"))
    )
    (net (code "41") (name "Net-(EPD_C6-Pad1)") (class "Default")
      (node (ref "EPD_C6") (pin "1") (pinfunction "1_1") (pintype "passive"))
      (node (ref "J3") (pin "18") (pinfunction "18_18") (pintype "bidirectional"))
    )
    (net (code "42") (name "Net-(EPD_C7-Pad1)") (class "Default")
      (node (ref "EPD_C7") (pin "1") (pinfunction "1_1") (pintype "passive"))
      (node (ref "J3") (pin "19") (pinfunction "19_19") (pintype "bidirectional"))
    )
    (net (code "43") (name "Net-(EPD_C8-Pad1)") (class "Default")
      (node (ref "EPD_C8") (pin "1") (pinfunction "1_1") (pintype "passive"))
      (node (ref "J3") (pin "20") (pinfunction "20_20") (pintype "bidirectional"))
    )
    (net (code "44") (name "Net-(EPD_C10-Pad1)") (class "Default")
      (node (ref "EPD_C10") (pin "1") (pinfunction "1_1") (pintype "passive"))
      (node (ref "J3") (pin "22") (pinfunction "22_22") (pintype "bidirectional"))
    )
    (net (code "45") (name "Net-(EPD_C12-Pad1)") (class "Default")
      (node (ref "EPD_C12") (pin "1") (pinfunction "1_1") (pintype "passive"))
      (node (ref "J3") (pin "24") (pinfunction "24_24") (pintype "bidirectional"))
    )
    (net (code "46") (name "Net-(IC1-TS{slash}MR)") (class "Default")
      (node (ref "IC1") (pin "D1") (pinfunction "TS/MR_D1") (pintype "bidirectional"))
      (node (ref "R9") (pin "2") (pinfunction "2_2") (pintype "bidirectional"))
    )
    (net (code "47") (name "Net-(IC2-REG)") (class "Default")
      (node (ref "C32") (pin "2") (pinfunction "2_2") (pintype "passive"))
      (node (ref "IC2") (pin "A2") (pinfunction "REG_A2") (pintype "bidirectional"))
    )
    (net (code "48") (name "Net-(IC3-SDO)") (class "Default")
      (node (ref "IC3") (pin "1") (pinfunction "SDO_1") (pintype "bidirectional"))
      (node (ref "R3") (pin "2") (pinfunction "2_2") (pintype "bidirectional"))
    )
    (net (code "49") (name "Net-(IC9-SCL)") (class "Default")
      (node (ref "IC9") (pin "D1") (pinfunction "SCL_D1") (pintype "bidirectional"))
      (node (ref "R4") (pin "2") (pinfunction "2_2") (pintype "bidirectional"))
    )
    (net (code "50") (name "Net-(IC9-SDA)") (class "Default")
      (node (ref "IC9") (pin "E1") (pinfunction "SDA_E1") (pintype "bidirectional"))
      (node (ref "R2") (pin "2") (pinfunction "2_2") (pintype "bidirectional"))
    )
    (net (code "51") (name "Net-(J5-CC1)") (class "Default")
      (node (ref "J5") (pin "A5") (pinfunction "CC1_A5") (pintype "bidirectional"))
      (node (ref "R1_USB1") (pin "2") (pinfunction "2_2") (pintype "bidirectional"))
    )
    (net (code "52") (name "Net-(J5-CC2)") (class "Default")
      (node (ref "J5") (pin "B5") (pinfunction "CC2_B5") (pintype "bidirectional"))
      (node (ref "R2_USB2") (pin "1") (pinfunction "1_1") (pintype "bidirectional"))
    )
    (net (code "53") (name "Net-(L2-Pad2)") (class "Default")
      (node (ref "L2") (pin "2") (pinfunction "2_2") (pintype "passive"))
      (node (ref "L3") (pin "1") (pinfunction "1_1") (pintype "passive"))
    )
    (net (code "54") (name "Net-(R1_EP_DR1-Pad1)") (class "Default")
      (node (ref "R1_EP_DR1") (pin "1") (pinfunction "1_1") (pintype "bidirectional"))
      (node (ref "R_TYPE_SEL1") (pin "2") (pinfunction "2_2") (pintype "bidirectional"))
      (node (ref "SJ1") (pin "2") (pinfunction "2_2") (pintype "passive"))
    )
    (net (code "55") (name "Net-(U1-ANT)") (class "Default")
      (node (ref "C3") (pin "1") (pinfunction "1_1") (pintype "passive"))
      (node (ref "L1") (pin "1") (pinfunction "1_1") (pintype "passive"))
      (node (ref "U1") (pin "P$H23") (pinfunction "ANT_P$H23") (pintype "bidirectional"))
    )
    (net (code "56") (name "Net-(U1-DCC)") (class "Default")
      (node (ref "L2") (pin "1") (pinfunction "1_1") (pintype "passive"))
      (node (ref "U1") (pin "P$B3") (pinfunction "DCC_P$B3") (pintype "output"))
    )
    (net (code "57") (name "Net-(U1-DEC2)") (class "Default")
      (node (ref "C13") (pin "1") (pinfunction "1_1") (pintype "passive"))
      (node (ref "U1") (pin "P$A18") (pinfunction "DEC2_P$A18") (pintype "bidirectional"))
    )
    (net (code "58") (name "Net-(U1-DEC3V3)") (class "Default")
      (node (ref "C20") (pin "1") (pinfunction "1_1") (pintype "passive"))
      (node (ref "U1") (pin "P$AC5") (pinfunction "DEC3V3_P$AC5") (pintype "bidirectional"))
    )
    (net (code "59") (name "Net-(U1-DEC5)") (class "Default")
      (node (ref "C9") (pin "1") (pinfunction "1_1") (pintype "passive"))
      (node (ref "U1") (pin "P$N24") (pinfunction "DEC5_P$N24") (pintype "bidirectional"))
    )
    (net (code "60") (name "Net-(U1-XC1)") (class "Default")
      (node (ref "C1") (pin "1") (pinfunction "1_1") (pintype "passive"))
      (node (ref "U1") (pin "P$B24") (pinfunction "XC1_P$B24") (pintype "input"))
      (node (ref "X1") (pin "1") (pinfunction "1_1") (pintype "passive"))
    )
    (net (code "61") (name "Net-(U1-XC2)") (class "Default")
      (node (ref "C2") (pin "1") (pinfunction "1_1") (pintype "passive"))
      (node (ref "U1") (pin "P$A23") (pinfunction "XC2_P$A23") (pintype "output"))
      (node (ref "X1") (pin "3") (pinfunction "3_3") (pintype "passive"))
    )
    (net (code "62") (name "OUT+") (class "Default")
      (node (ref "IC2") (pin "A3") (pinfunction "OUT+_A3") (pintype "bidirectional"))
      (node (ref "TP_OP") (pin "TP") (pinfunction "TP_TP") (pintype "input"))
    )
    (net (code "63") (name "OUT-") (class "Default")
      (node (ref "IC2") (pin "C3") (pinfunction "OUT-_C3") (pintype "bidirectional"))
      (node (ref "TP_ON") (pin "TP") (pinfunction "TP_TP") (pintype "input"))
    )
    (net (code "64") (name "P0.00{slash}XL1") (class "Default")
      (node (ref "C17") (pin "2") (pinfunction "2_2") (pintype "passive"))
      (node (ref "U1") (pin "P$D2") (pinfunction "P0.00/XL1_P$D2") (pintype "bidirectional"))
      (node (ref "X2") (pin "1") (pinfunction "1_1") (pintype "passive"))
    )
    (net (code "65") (name "P0.01{slash}XL2") (class "Default")
      (node (ref "C18") (pin "2") (pinfunction "2_2") (pintype "passive"))
      (node (ref "U1") (pin "P$F2") (pinfunction "P0.01/XL2_P$F2") (pintype "bidirectional"))
      (node (ref "X2") (pin "2") (pinfunction "2_2") (pintype "passive"))
    )
    (net (code "66") (name "P0.04") (class "Default")
      (node (ref "U1") (pin "P$J1") (pinfunction "P0.04/AIN2_P$J1") (pintype "bidirectional"))
    )
    (net (code "67") (name "P0.09") (class "Default")
      (node (ref "U1") (pin "P$L24") (pinfunction "P0.09/NFC1_P$L24") (pintype "bidirectional"))
    )
    (net (code "68") (name "P0.13{slash}1.5D") (class "Default")
      (node (ref "C30") (pin "2") (pinfunction "2_2") (pintype "passive"))
      (node (ref "R5") (pin "1") (pinfunction "1_1") (pintype "bidirectional"))
      (node (ref "SW_UP") (pin "2") (pinfunction "2_2") (pintype "passive"))
    )
    (net (code "69") (name "P0.13{slash}2.6C") (class "Default")
      (node (ref "U1") (pin "P$AD8") (pinfunction "P0.13_P$AD8") (pintype "bidirectional"))
    )
    (net (code "70") (name "P0.14{slash}1.5D") (class "Default")
      (node (ref "C31") (pin "2") (pinfunction "2_2") (pintype "passive"))
      (node (ref "R8") (pin "1") (pinfunction "1_1") (pintype "bidirectional"))
      (node (ref "SW_ENT") (pin "2") (pinfunction "2_2") (pintype "passive"))
    )
    (net (code "71") (name "P0.14{slash}2.7C") (class "Default")
      (node (ref "U1") (pin "P$AC9") (pinfunction "P0.14_P$AC9") (pintype "bidirectional"))
    )
    (net (code "72") (name "P0.19") (class "Default")
      (node (ref "U1") (pin "P$AC15") (pinfunction "P0.19_P$AC15") (pintype "bidirectional"))
    )
    (net (code "73") (name "P0.20") (class "Default")
      (node (ref "U1") (pin "P$AD16") (pinfunction "P0.20_P$AD16") (pintype "bidirectional"))
    )
    (net (code "74") (name "P0.21") (class "Default")
      (node (ref "U1") (pin "P$AC17") (pinfunction "P0.21_P$AC17") (pintype "bidirectional"))
    )
    (net (code "75") (name "P0.22") (class "Default")
      (node (ref "U1") (pin "P$AD18") (pinfunction "P0.22_P$AD18") (pintype "bidirectional"))
    )
    (net (code "76") (name "P0.23") (class "Default")
      (node (ref "U1") (pin "P$AC19") (pinfunction "P0.23_P$AC19") (pintype "bidirectional"))
    )
    (net (code "77") (name "P0.24") (class "Default")
      (node (ref "U1") (pin "P$AD20") (pinfunction "P0.24_P$AD20") (pintype "bidirectional"))
    )
    (net (code "78") (name "P0.25") (class "Default")
      (node (ref "U1") (pin "P$AC21") (pinfunction "P0.25_P$AC21") (pintype "bidirectional"))
    )
    (net (code "79") (name "P0.26") (class "Default")
      (node (ref "U1") (pin "P$G1") (pinfunction "P0.26_P$G1") (pintype "bidirectional"))
    )
    (net (code "80") (name "P0.27") (class "Default")
      (node (ref "U1") (pin "P$H2") (pinfunction "P0.27_P$H2") (pintype "bidirectional"))
    )
    (net (code "81") (name "P0.28") (class "Default")
      (node (ref "U1") (pin "P$B11") (pinfunction "P0.28/AIN4_P$B11") (pintype "bidirectional"))
    )
    (net (code "82") (name "P0.29") (class "Default")
      (node (ref "U1") (pin "P$A10") (pinfunction "P0.29/AIN5_P$A10") (pintype "bidirectional"))
    )
    (net (code "83") (name "P0.30") (class "Default")
      (node (ref "U1") (pin "P$B9") (pinfunction "P0.30/AIN6_P$B9") (pintype "bidirectional"))
    )
    (net (code "84") (name "P0.31") (class "Default")
      (node (ref "U1") (pin "P$A8") (pinfunction "P0.31/AIN7_P$A8") (pintype "bidirectional"))
    )
    (net (code "85") (name "P1.01{slash}1.6C") (class "Default")
      (node (ref "DMG2305UX-7") (pin "1") (pinfunction "G_1") (pintype "bidirectional"))
      (node (ref "R_PWR_EPD1") (pin "1") (pinfunction "1_1") (pintype "bidirectional"))
    )
    (net (code "86") (name "P1.01{slash}2.4B") (class "Default")
      (node (ref "U1") (pin "P$Y23") (pinfunction "P1.01_P$Y23") (pintype "bidirectional"))
    )
    (net (code "87") (name "P1.02{slash}1.6C") (class "Default")
      (node (ref "C29") (pin "2") (pinfunction "2_2") (pintype "passive"))
      (node (ref "R7") (pin "1") (pinfunction "1_1") (pintype "bidirectional"))
      (node (ref "SW_DN") (pin "2") (pinfunction "2_2") (pintype "passive"))
    )
    (net (code "88") (name "P1.02{slash}2.8C") (class "Default")
      (node (ref "U1") (pin "P$W24") (pinfunction "P1.02_P$W24") (pintype "bidirectional"))
    )
    (net (code "89") (name "P1.03") (class "Default")
      (node (ref "U1") (pin "P$V23") (pinfunction "P1.03_P$V23") (pintype "bidirectional"))
    )
    (net (code "90") (name "P1.04") (class "Default")
      (node (ref "U1") (pin "P$U24") (pinfunction "P1.04_P$U24") (pintype "bidirectional"))
    )
    (net (code "91") (name "P1.05") (class "Default")
      (node (ref "U1") (pin "P$T23") (pinfunction "P1.05_P$T23") (pintype "bidirectional"))
    )
    (net (code "92") (name "P1.06") (class "Default")
      (node (ref "U1") (pin "P$R24") (pinfunction "P1.06_P$R24") (pintype "bidirectional"))
    )
    (net (code "93") (name "P1.07") (class "Default")
      (node (ref "U1") (pin "P$P23") (pinfunction "P1.07_P$P23") (pintype "bidirectional"))
    )
    (net (code "94") (name "P1.09") (class "Default")
      (node (ref "U1") (pin "P$R1") (pinfunction "P1.09_P$R1") (pintype "bidirectional"))
    )
    (net (code "95") (name "P1.10") (class "Default")
      (node (ref "U1") (pin "P$A20") (pinfunction "P1.10_P$A20") (pintype "bidirectional"))
    )
    (net (code "96") (name "P1.11") (class "Default")
      (node (ref "U1") (pin "P$B19") (pinfunction "P1.11_P$B19") (pintype "bidirectional"))
    )
    (net (code "97") (name "P1.12") (class "Default")
      (node (ref "U1") (pin "P$B17") (pinfunction "P1.12_P$B17") (pintype "bidirectional"))
    )
    (net (code "98") (name "P1.13") (class "Default")
      (node (ref "U1") (pin "P$A16") (pinfunction "P1.13_P$A16") (pintype "bidirectional"))
    )
    (net (code "99") (name "P1.14") (class "Default")
      (node (ref "U1") (pin "P$B15") (pinfunction "P1.14_P$B15") (pintype "bidirectional"))
    )
    (net (code "100") (name "P1.15") (class "Default")
      (node (ref "U1") (pin "P$A14") (pinfunction "P1.15_P$A14") (pintype "bidirectional"))
    )
    (net (code "101") (name "PMIC_INT") (class "Default")
      (node (ref "IC1") (pin "A1") (pinfunction "~{INT}_A1") (pintype "bidirectional"))
      (node (ref "U1") (pin "P$T2") (pinfunction "P0.11_P$T2") (pintype "bidirectional"))
    )
    (net (code "102") (name "PREVGH") (class "Default")
      (node (ref "D5") (pin "1") (pinfunction "K_1") (pintype "bidirectional"))
      (node (ref "EPD_C15") (pin "1") (pinfunction "1_1") (pintype "passive"))
      (node (ref "J3") (pin "21") (pinfunction "21_21") (pintype "bidirectional"))
    )
    (net (code "103") (name "PREVGL") (class "Default")
      (node (ref "D2") (pin "2") (pinfunction "A_2") (pintype "bidirectional"))
      (node (ref "EPD_C11") (pin "1") (pinfunction "1_1") (pintype "passive"))
      (node (ref "J3") (pin "23") (pinfunction "23_23") (pintype "bidirectional"))
    )
    (net (code "104") (name "RESE") (class "Default")
      (node (ref "J3") (pin "3") (pinfunction "3_3") (pintype "bidirectional"))
      (node (ref "Q3") (pin "2") (pinfunction "S_2") (pintype "bidirectional"))
      (node (ref "R1_EP_DR1") (pin "2") (pinfunction "2_2") (pintype "bidirectional"))
    )
    (net (code "105") (name "RESET") (class "Default")
      (node (ref "J2") (pin "6") (pinfunction "6_6") (pintype "bidirectional"))
      (node (ref "TP_RESET") (pin "TP") (pinfunction "TP_TP") (pintype "input"))
      (node (ref "U1") (pin "P$AC13") (pinfunction "P0.18/RESET_P$AC13") (pintype "bidirectional"))
    )
    (net (code "106") (name "RF") (class "Default")
      (node (ref "ANT1") (pin "1") (pinfunction "FEED_1") (pintype "input"))
      (node (ref "C22") (pin "1") (pinfunction "1_1") (pintype "passive"))
      (node (ref "C4") (pin "1") (pinfunction "1_1") (pintype "passive"))
      (node (ref "L1") (pin "2") (pinfunction "2_2") (pintype "passive"))
    )
    (net (code "107") (name "SCK{slash}1.5B") (class "Default")
      (node (ref "J3") (pin "13") (pinfunction "13_13") (pintype "bidirectional"))
    )
    (net (code "108") (name "SCK{slash}2.2D") (class "Default")
      (node (ref "U1") (pin "P$A12") (pinfunction "P0.02/AIN0_P$A12") (pintype "bidirectional"))
    )
    (net (code "109") (name "SCL{slash}1.4C") (class "Default")
      (node (ref "IC2") (pin "C1") (pinfunction "SCL_C1") (pintype "bidirectional"))
      (node (ref "U2") (pin "7") (pinfunction "SCL_7") (pintype "input"))
    )
    (net (code "110") (name "SCL{slash}2.4C") (class "Default")
      (node (ref "IC1") (pin "B1") (pinfunction "SCL_B1") (pintype "bidirectional"))
      (node (ref "IC3") (pin "12") (pinfunction "SCX_12") (pintype "bidirectional"))
      (node (ref "R17") (pin "2") (pinfunction "2_2") (pintype "bidirectional"))
      (node (ref "R4") (pin "1") (pinfunction "1_1") (pintype "bidirectional"))
      (node (ref "TP_SCL") (pin "TP") (pinfunction "TP_TP") (pintype "input"))
      (node (ref "U1") (pin "P$M2") (pinfunction "P0.07_P$M2") (pintype "bidirectional"))
    )
    (net (code "111") (name "SDA{slash}1.4C") (class "Default")
      (node (ref "IC2") (pin "B2") (pinfunction "SDA_B2") (pintype "bidirectional"))
      (node (ref "U2") (pin "8") (pinfunction "SDA_8") (pintype "bidirectional"))
    )
    (net (code "112") (name "SDA{slash}2.4C") (class "Default")
      (node (ref "IC1") (pin "C1") (pinfunction "SDA_C1") (pintype "bidirectional"))
      (node (ref "IC3") (pin "2") (pinfunction "SDX_2") (pintype "bidirectional"))
      (node (ref "R18") (pin "2") (pinfunction "2_2") (pintype "bidirectional"))
      (node (ref "R2") (pin "1") (pinfunction "1_1") (pintype "bidirectional"))
      (node (ref "TP_SDA") (pin "TP") (pinfunction "TP_TP") (pintype "input"))
      (node (ref "U1") (pin "P$L1") (pinfunction "P0.06_P$L1") (pintype "bidirectional"))
    )
    (net (code "113") (name "SWDCLK") (class "Default")
      (node (ref "J2") (pin "4") (pinfunction "4_4") (pintype "bidirectional"))
      (node (ref "TP_SWDCLK") (pin "TP") (pinfunction "TP_TP") (pintype "input"))
      (node (ref "U1") (pin "P$AA24") (pinfunction "SWDCLK_P$AA24") (pintype "input"))
    )
    (net (code "114") (name "SWDIO") (class "Default")
      (node (ref "J2") (pin "2") (pinfunction "2_2") (pintype "bidirectional"))
      (node (ref "TP_SWDIO") (pin "TP") (pinfunction "TP_TP") (pintype "input"))
      (node (ref "U1") (pin "P$AC24") (pinfunction "SWDIO_P$AC24") (pintype "bidirectional"))
    )
    (net (code "115") (name "SWO") (class "Default")
      (node (ref "TP_SWO") (pin "TP") (pinfunction "TP_TP") (pintype "input"))
      (node (ref "U1") (pin "P$AD22") (pinfunction "P1.00_P$AD22") (pintype "bidirectional"))
    )
    (net (code "116") (name "VBAT{slash}1.2A") (class "Default")
      (node (ref "C27") (pin "2") (pinfunction "2_2") (pintype "passive"))
      (node (ref "TP_VBAT1") (pin "TP") (pinfunction "TP_TP") (pintype "input"))
      (node (ref "U2") (pin "2") (pinfunction "CELL_2") (pintype "power_in"))
      (node (ref "U2") (pin "3") (pinfunction "VDD_3") (pintype "power_in"))
    )
    (net (code "117") (name "VBAT{slash}2.5C") (class "Default")
      (node (ref "C37") (pin "2") (pinfunction "2_2") (pintype "passive"))
      (node (ref "IC1") (pin "C2") (pinfunction "BAT_C2") (pintype "bidirectional"))
    )
    (net (code "118") (name "VBUS{slash}1.5D") (class "Default")
      (node (ref "C42") (pin "1") (pinfunction "1_1") (pintype "passive"))
      (node (ref "C43") (pin "2") (pinfunction "2_2") (pintype "passive"))
      (node (ref "D3") (pin "5") (pinfunction "VBUS_5") (pintype "bidirectional"))
      (node (ref "J5") (pin "A4_B9") (pinfunction "VBUS_A4_B9") (pintype "power_in"))
      (node (ref "J5") (pin "A9_B4") (pinfunction "VBUS_A9_B4") (pintype "power_in"))
    )
    (net (code "119") (name "VBUS{slash}2.6D") (class "Default")
      (node (ref "C21") (pin "1") (pinfunction "1_1") (pintype "passive"))
      (node (ref "C38") (pin "2") (pinfunction "2_2") (pintype "passive"))
      (node (ref "IC1") (pin "A2") (pinfunction "IN_A2") (pintype "bidirectional"))
      (node (ref "U1") (pin "P$AD2") (pinfunction "VBUS_P$AD2") (pintype "power_in"))
    )
    (net (code "120") (name "VREG") (class "Default")
      (node (ref "C23") (pin "2") (pinfunction "2_2") (pintype "passive"))
      (node (ref "C24") (pin "1") (pinfunction "1_1") (pintype "passive"))
      (node (ref "C39") (pin "2") (pinfunction "2_2") (pintype "passive"))
      (node (ref "IC1") (pin "B2") (pinfunction "SYS_B2") (pintype "bidirectional"))
      (node (ref "IC9") (pin "A1") (pinfunction "EN_A1") (pintype "bidirectional"))
      (node (ref "IC9") (pin "A2") (pinfunction "VIN_1_A2") (pintype "bidirectional"))
      (node (ref "IC9") (pin "A3") (pinfunction "VIN_2_A3") (pintype "bidirectional"))
      (node (ref "TP_VREG") (pin "TP") (pinfunction "TP_TP") (pintype "input"))
    )
    (net (code "121") (name "unconnected-(ANT1-NC-Pad2)") (class "Default")
      (node (ref "ANT1") (pin "2") (pinfunction "NC_2") (pintype "no_connect"))
    )
    (net (code "122") (name "unconnected-(IC3-ASCL-Pad11)") (class "Default")
      (node (ref "IC3") (pin "11") (pinfunction "ASCL_11") (pintype "bidirectional"))
    )
    (net (code "123") (name "unconnected-(IC3-ASDA-Pad4)") (class "Default")
      (node (ref "IC3") (pin "4") (pinfunction "ASDA_4") (pintype "bidirectional"))
    )
    (net (code "124") (name "unconnected-(IC9-SW1_2-PadB3)") (class "Default")
      (node (ref "IC9") (pin "B3") (pinfunction "SW1_2_B3") (pintype "bidirectional"))
    )
    (net (code "125") (name "unconnected-(J3-Pad1)") (class "Default")
      (node (ref "J3") (pin "1") (pinfunction "1_1") (pintype "bidirectional"))
    )
    (net (code "126") (name "unconnected-(J3-Pad6)") (class "Default")
      (node (ref "J3") (pin "6") (pinfunction "6_6") (pintype "bidirectional"))
    )
    (net (code "127") (name "unconnected-(J3-Pad7)") (class "Default")
      (node (ref "J3") (pin "7") (pinfunction "7_7") (pintype "bidirectional"))
    )
    (net (code "128") (name "unconnected-(J5-SBU1-PadA8)") (class "Default")
      (node (ref "J5") (pin "A8") (pinfunction "SBU1_A8") (pintype "bidirectional"))
    )
    (net (code "129") (name "unconnected-(J5-SBU2-PadB8)") (class "Default")
      (node (ref "J5") (pin "B8") (pinfunction "SBU2_B8") (pintype "bidirectional"))
    )
    (net (code "130") (name "unconnected-(U1-DCCH-PadP$AB2)") (class "Default")
      (node (ref "U1") (pin "P$AB2") (pinfunction "DCCH_P$AB2") (pintype "bidirectional"))
    )
  )
)
